# reg-board.net
KiCad netlist of a schematic drawn in EAGLE
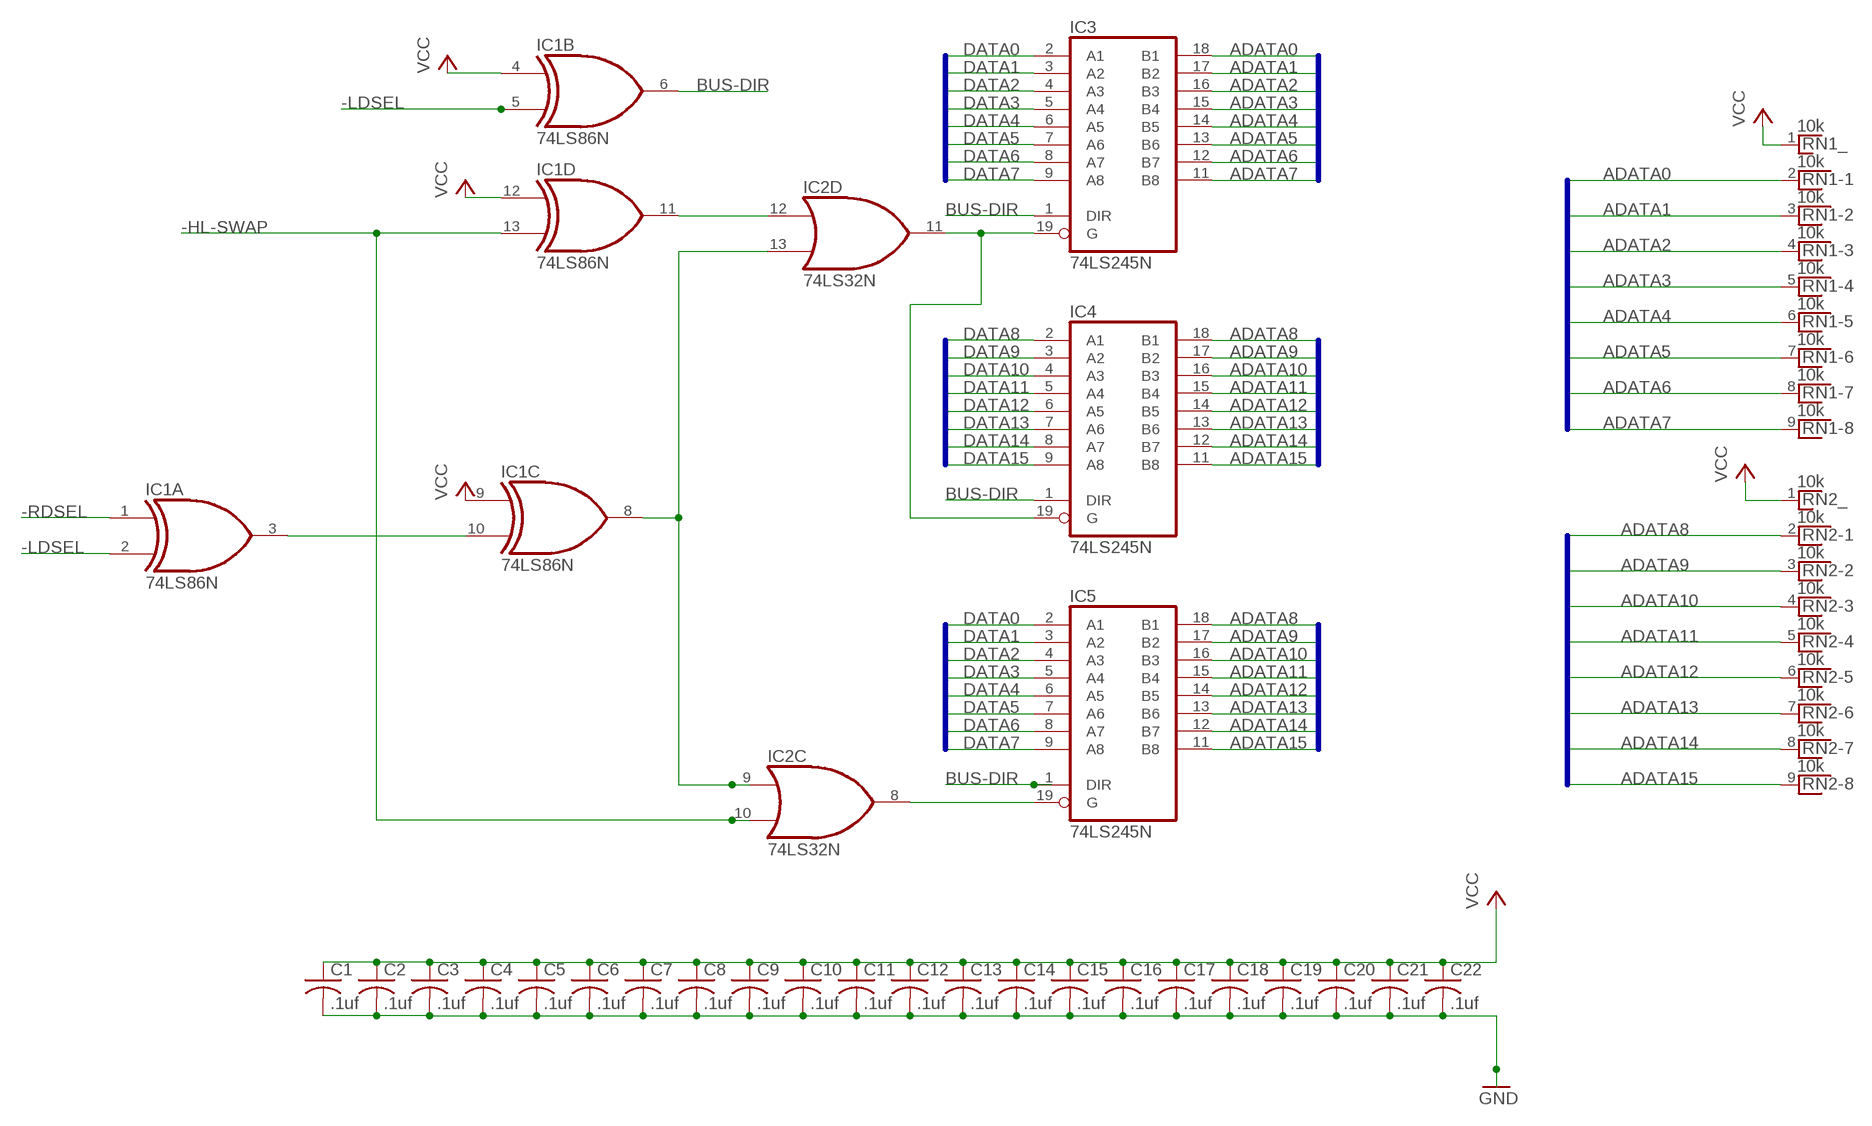
[diagram p0: schematic, sheet 1]
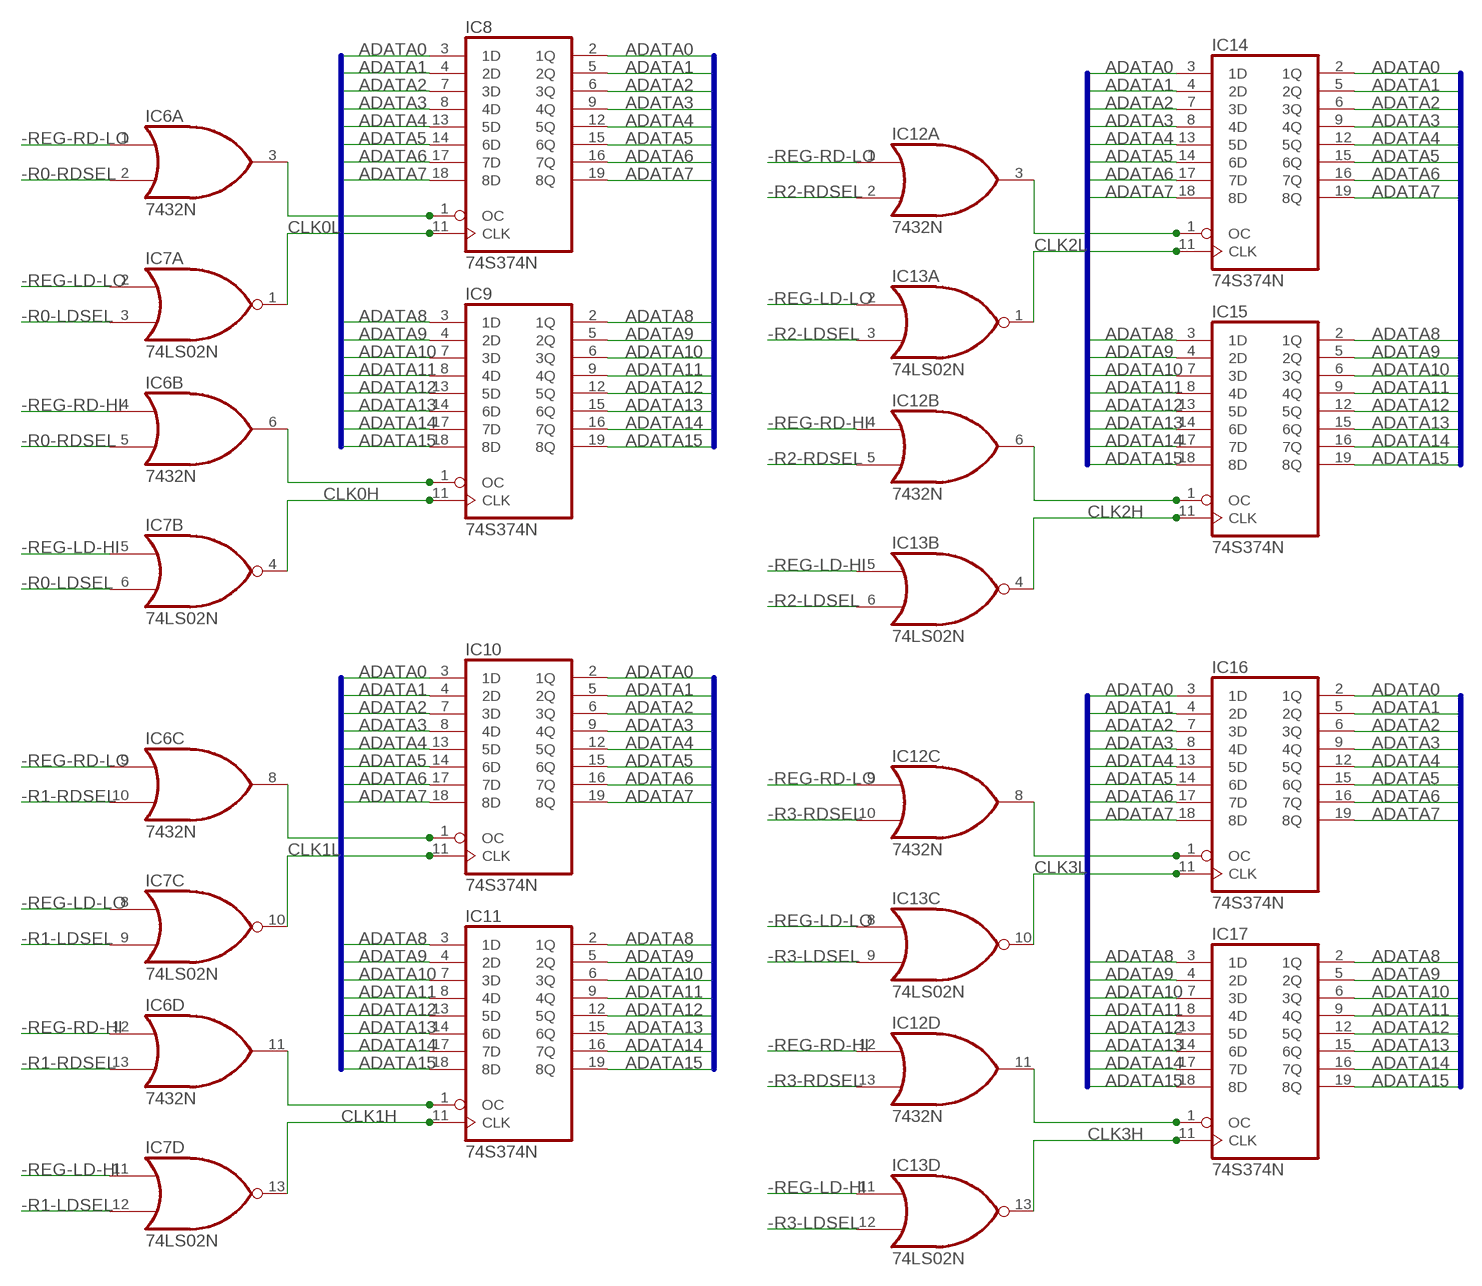
[diagram p1: schematic, sheet 2]
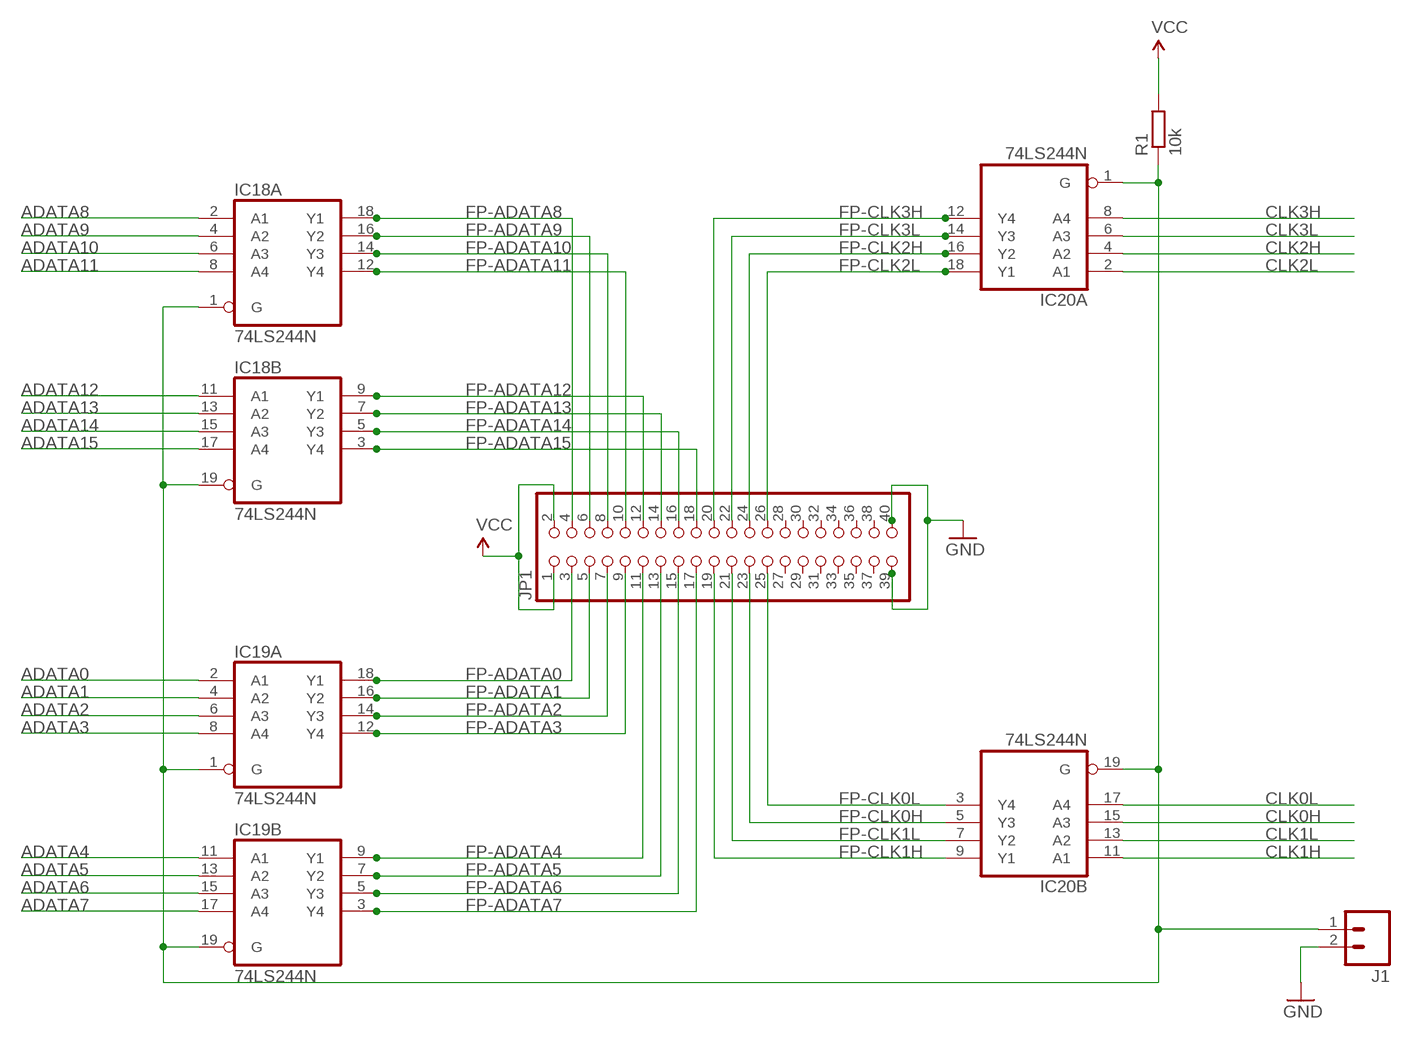
[diagram p2: schematic, sheet 3]
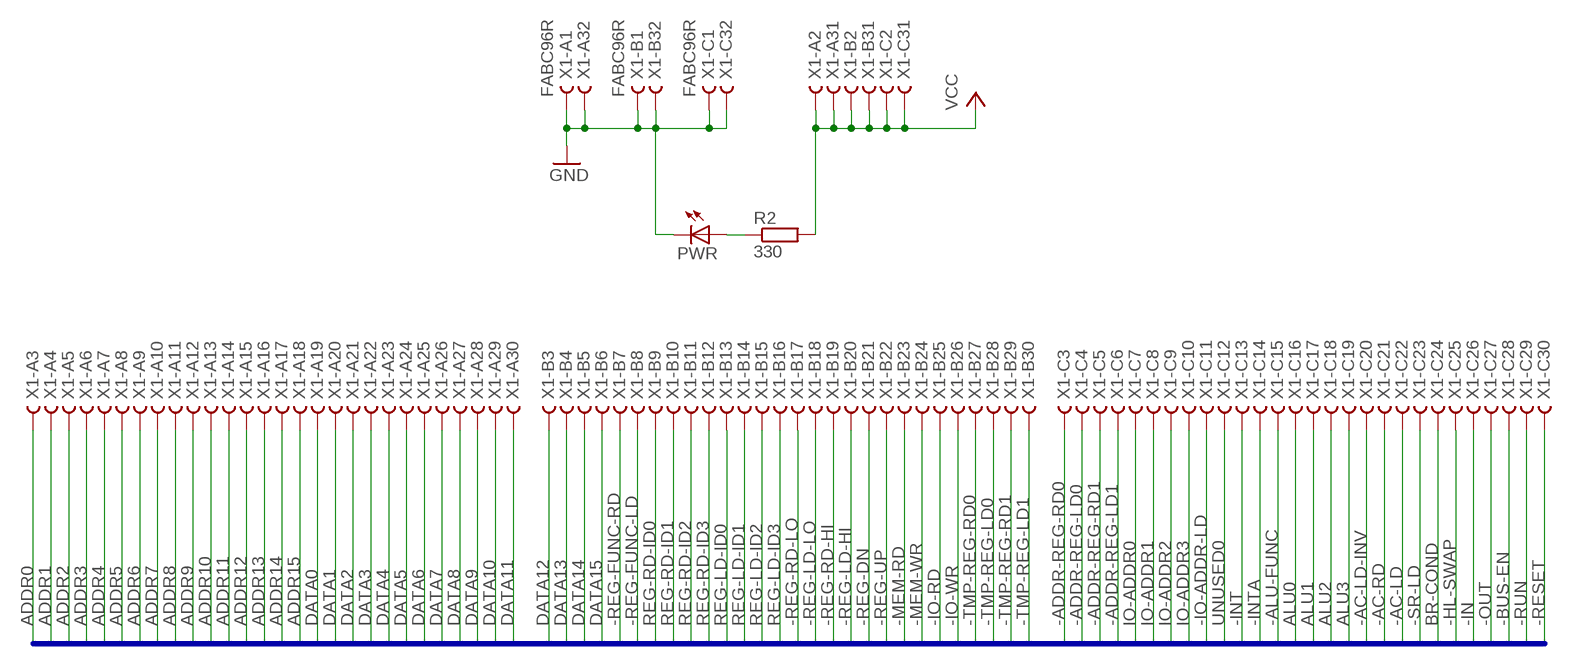
[diagram p3: schematic, sheet 4]
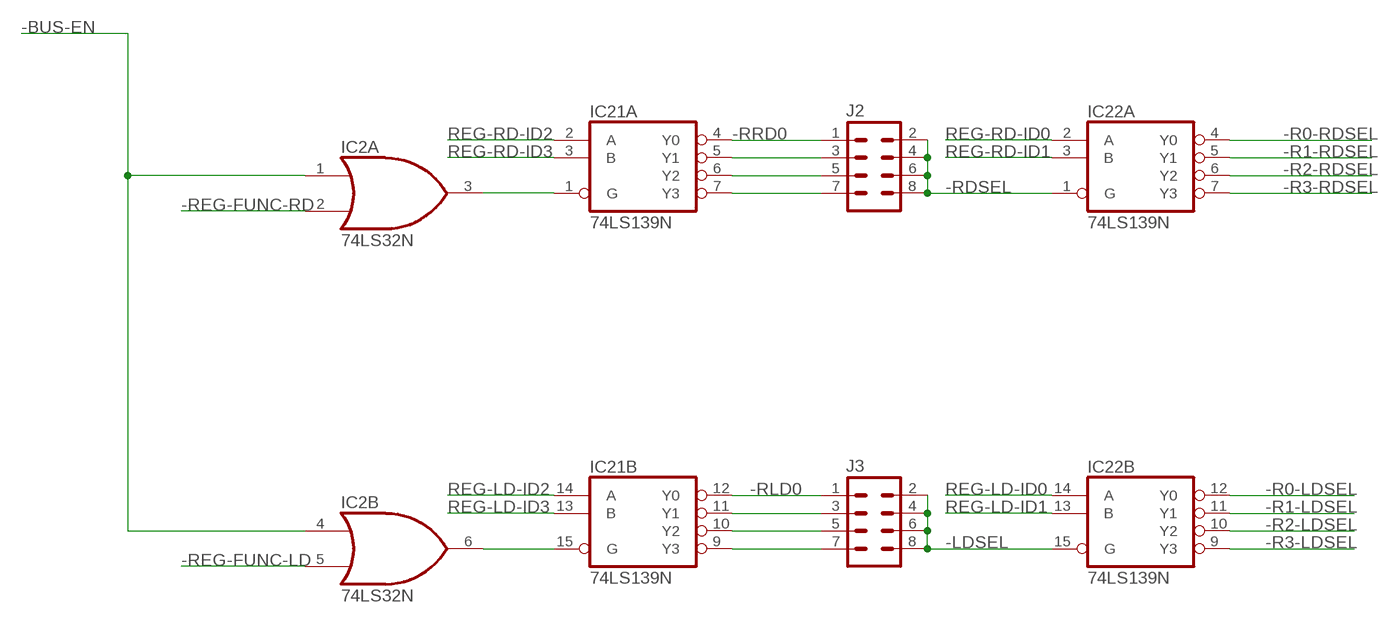
[diagram p4: schematic, sheet 5]

(export (version "E")
  (design (tool "Eeschema 10.0.6"))
  (components
    (comp (ref "PWR")
      (value "LED5MM")
      (footprint "eagle-import:LED5MM")
      (libsource (lib "eagle-import") (part "LED5MM"))
    )
    (comp (ref "R2")
      (value "330")
      (footprint "eagle-import:0207_10")
      (libsource (lib "eagle-import") (part "R0207/10"))
    )
    (comp (ref "X1")
      (value "FABC96R")
      (footprint "eagle-import:FABC96R")
      (libsource (lib "eagle-import") (part "FABC96R"))
    )
    (comp (ref "IC6")
      (value "7432N")
      (footprint "eagle-import:DIL14")
      (libsource (lib "eagle-import") (part "7432N"))
    )
    (comp (ref "IC7")
      (value "74LS02N")
      (footprint "eagle-import:DIL14")
      (libsource (lib "eagle-import") (part "7402NLS"))
    )
    (comp (ref "IC8")
      (value "74S374N")
      (footprint "eagle-import:DIL20")
      (libsource (lib "eagle-import") (part "74374NS"))
    )
    (comp (ref "IC9")
      (value "74S374N")
      (footprint "eagle-import:DIL20")
      (libsource (lib "eagle-import") (part "74374NS"))
    )
    (comp (ref "IC10")
      (value "74S374N")
      (footprint "eagle-import:DIL20")
      (libsource (lib "eagle-import") (part "74374NS"))
    )
    (comp (ref "IC11")
      (value "74S374N")
      (footprint "eagle-import:DIL20")
      (libsource (lib "eagle-import") (part "74374NS"))
    )
    (comp (ref "IC12")
      (value "7432N")
      (footprint "eagle-import:DIL14")
      (libsource (lib "eagle-import") (part "7432N"))
    )
    (comp (ref "IC13")
      (value "74LS02N")
      (footprint "eagle-import:DIL14")
      (libsource (lib "eagle-import") (part "7402NLS"))
    )
    (comp (ref "IC14")
      (value "74S374N")
      (footprint "eagle-import:DIL20")
      (libsource (lib "eagle-import") (part "74374NS"))
    )
    (comp (ref "IC15")
      (value "74S374N")
      (footprint "eagle-import:DIL20")
      (libsource (lib "eagle-import") (part "74374NS"))
    )
    (comp (ref "IC16")
      (value "74S374N")
      (footprint "eagle-import:DIL20")
      (libsource (lib "eagle-import") (part "74374NS"))
    )
    (comp (ref "IC17")
      (value "74S374N")
      (footprint "eagle-import:DIL20")
      (libsource (lib "eagle-import") (part "74374NS"))
    )
    (comp (ref "C1")
      (value ".1uf")
      (footprint "eagle-import:C025-040X050")
      (libsource (lib "eagle-import") (part "C-US025-040X050"))
    )
    (comp (ref "C2")
      (value ".1uf")
      (footprint "eagle-import:C025-040X050")
      (libsource (lib "eagle-import") (part "C-US025-040X050"))
    )
    (comp (ref "C3")
      (value ".1uf")
      (footprint "eagle-import:C025-040X050")
      (libsource (lib "eagle-import") (part "C-US025-040X050"))
    )
    (comp (ref "C4")
      (value ".1uf")
      (footprint "eagle-import:C025-040X050")
      (libsource (lib "eagle-import") (part "C-US025-040X050"))
    )
    (comp (ref "C5")
      (value ".1uf")
      (footprint "eagle-import:C025-040X050")
      (libsource (lib "eagle-import") (part "C-US025-040X050"))
    )
    (comp (ref "C6")
      (value ".1uf")
      (footprint "eagle-import:C025-040X050")
      (libsource (lib "eagle-import") (part "C-US025-040X050"))
    )
    (comp (ref "C7")
      (value ".1uf")
      (footprint "eagle-import:C025-040X050")
      (libsource (lib "eagle-import") (part "C-US025-040X050"))
    )
    (comp (ref "C8")
      (value ".1uf")
      (footprint "eagle-import:C025-040X050")
      (libsource (lib "eagle-import") (part "C-US025-040X050"))
    )
    (comp (ref "C9")
      (value ".1uf")
      (footprint "eagle-import:C025-040X050")
      (libsource (lib "eagle-import") (part "C-US025-040X050"))
    )
    (comp (ref "C10")
      (value ".1uf")
      (footprint "eagle-import:C025-040X050")
      (libsource (lib "eagle-import") (part "C-US025-040X050"))
    )
    (comp (ref "C11")
      (value ".1uf")
      (footprint "eagle-import:C025-040X050")
      (libsource (lib "eagle-import") (part "C-US025-040X050"))
    )
    (comp (ref "C12")
      (value ".1uf")
      (footprint "eagle-import:C025-040X050")
      (libsource (lib "eagle-import") (part "C-US025-040X050"))
    )
    (comp (ref "C13")
      (value ".1uf")
      (footprint "eagle-import:C025-040X050")
      (libsource (lib "eagle-import") (part "C-US025-040X050"))
    )
    (comp (ref "C14")
      (value ".1uf")
      (footprint "eagle-import:C025-040X050")
      (libsource (lib "eagle-import") (part "C-US025-040X050"))
    )
    (comp (ref "C15")
      (value ".1uf")
      (footprint "eagle-import:C025-040X050")
      (libsource (lib "eagle-import") (part "C-US025-040X050"))
    )
    (comp (ref "C16")
      (value ".1uf")
      (footprint "eagle-import:C025-040X050")
      (libsource (lib "eagle-import") (part "C-US025-040X050"))
    )
    (comp (ref "C17")
      (value ".1uf")
      (footprint "eagle-import:C025-040X050")
      (libsource (lib "eagle-import") (part "C-US025-040X050"))
    )
    (comp (ref "C18")
      (value ".1uf")
      (footprint "eagle-import:C025-040X050")
      (libsource (lib "eagle-import") (part "C-US025-040X050"))
    )
    (comp (ref "C19")
      (value ".1uf")
      (footprint "eagle-import:C025-040X050")
      (libsource (lib "eagle-import") (part "C-US025-040X050"))
    )
    (comp (ref "C20")
      (value ".1uf")
      (footprint "eagle-import:C025-040X050")
      (libsource (lib "eagle-import") (part "C-US025-040X050"))
    )
    (comp (ref "C21")
      (value ".1uf")
      (footprint "eagle-import:C025-040X050")
      (libsource (lib "eagle-import") (part "C-US025-040X050"))
    )
    (comp (ref "C22")
      (value ".1uf")
      (footprint "eagle-import:C025-040X050")
      (libsource (lib "eagle-import") (part "C-US025-040X050"))
    )
    (comp (ref "IC1")
      (value "74LS86N")
      (footprint "eagle-import:DIL14")
      (libsource (lib "eagle-import") (part "7486NLS"))
    )
    (comp (ref "IC2")
      (value "74LS32N")
      (footprint "eagle-import:DIL14")
      (libsource (lib "eagle-import") (part "74xx-us_88_7432NLS"))
    )
    (comp (ref "IC3")
      (value "74LS245N")
      (footprint "eagle-import:DIL20")
      (libsource (lib "eagle-import") (part "74245NLS"))
    )
    (comp (ref "IC4")
      (value "74LS245N")
      (footprint "eagle-import:DIL20")
      (libsource (lib "eagle-import") (part "74245NLS"))
    )
    (comp (ref "IC5")
      (value "74LS245N")
      (footprint "eagle-import:DIL20")
      (libsource (lib "eagle-import") (part "74245NLS"))
    )
    (comp (ref "RN1")
      (value "10k")
      (footprint "eagle-import:RN-9")
      (libsource (lib "eagle-import") (part "RNX8"))
    )
    (comp (ref "RN2")
      (value "10k")
      (footprint "eagle-import:RN-9")
      (libsource (lib "eagle-import") (part "RNX8"))
    )
    (comp (ref "IC18")
      (value "74LS244N")
      (footprint "eagle-import:DIL20")
      (libsource (lib "eagle-import") (part "74xx-us_74244NLS"))
    )
    (comp (ref "IC19")
      (value "74LS244N")
      (footprint "eagle-import:DIL20")
      (libsource (lib "eagle-import") (part "74xx-us_74244NLS"))
    )
    (comp (ref "IC20")
      (value "74LS244N")
      (footprint "eagle-import:DIL20")
      (libsource (lib "eagle-import") (part "74xx-us_74244NLS"))
    )
    (comp (ref "J1")
      (value "M02PTH")
      (footprint "eagle-import:1X02")
      (libsource (lib "eagle-import") (part "M02PTH"))
    )
    (comp (ref "JP1")
      (value "PINHD-2X20")
      (footprint "eagle-import:2X20")
      (libsource (lib "eagle-import") (part "PINHD-2X20"))
    )
    (comp (ref "R1")
      (value "10k")
      (footprint "eagle-import:0207_10")
      (libsource (lib "eagle-import") (part "R0207/10"))
    )
    (comp (ref "IC21")
      (value "74LS139N")
      (footprint "eagle-import:DIL16")
      (libsource (lib "eagle-import") (part "74139NLS"))
    )
    (comp (ref "IC22")
      (value "74LS139N")
      (footprint "eagle-import:DIL16")
      (libsource (lib "eagle-import") (part "74139NLS"))
    )
    (comp (ref "J2")
      (value "M04X2")
      (footprint "eagle-import:2X4")
      (libsource (lib "eagle-import") (part "M04X2"))
    )
    (comp (ref "J3")
      (value "M04X2")
      (footprint "eagle-import:2X4")
      (libsource (lib "eagle-import") (part "M04X2"))
    )
  )
  (nets
    (net (code "1") (name "-AC-LD") (class "Default")
      (node (ref "X1") (pin "C22") (pinfunction "B_C22") (pintype "passive"))
    )
    (net (code "2") (name "-AC-LD-INV") (class "Default")
      (node (ref "X1") (pin "C20") (pinfunction "B_C20") (pintype "passive"))
    )
    (net (code "3") (name "-AC-RD") (class "Default")
      (node (ref "X1") (pin "C21") (pinfunction "B_C21") (pintype "passive"))
    )
    (net (code "4") (name "-ADDR-REG-LD0") (class "Default")
      (node (ref "X1") (pin "C4") (pinfunction "B_C4") (pintype "passive"))
    )
    (net (code "5") (name "-ADDR-REG-LD1") (class "Default")
      (node (ref "X1") (pin "C6") (pinfunction "B_C6") (pintype "passive"))
    )
    (net (code "6") (name "-ADDR-REG-RD0") (class "Default")
      (node (ref "X1") (pin "C3") (pinfunction "B_C3") (pintype "passive"))
    )
    (net (code "7") (name "-ADDR-REG-RD1") (class "Default")
      (node (ref "X1") (pin "C5") (pinfunction "B_C5") (pintype "passive"))
    )
    (net (code "8") (name "-ALU-FUNC") (class "Default")
      (node (ref "X1") (pin "C15") (pinfunction "B_C15") (pintype "passive"))
    )
    (net (code "9") (name "-BUS-EN") (class "Default")
      (node (ref "IC2") (pin "1") (pinfunction "I0_1") (pintype "input"))
      (node (ref "IC2") (pin "4") (pinfunction "I0_4") (pintype "input"))
      (node (ref "X1") (pin "C28") (pinfunction "B_C28") (pintype "passive"))
    )
    (net (code "10") (name "-HL-SWAP") (class "Default")
      (node (ref "IC1") (pin "13") (pinfunction "I1_13") (pintype "input"))
      (node (ref "IC2") (pin "10") (pinfunction "I1_10") (pintype "input"))
      (node (ref "X1") (pin "C25") (pinfunction "B_C25") (pintype "passive"))
    )
    (net (code "11") (name "-IN") (class "Default")
      (node (ref "X1") (pin "C26") (pinfunction "B_C26") (pintype "passive"))
    )
    (net (code "12") (name "-INT") (class "Default")
      (node (ref "X1") (pin "C13") (pinfunction "B_C13") (pintype "passive"))
    )
    (net (code "13") (name "-INTA") (class "Default")
      (node (ref "X1") (pin "C14") (pinfunction "B_C14") (pintype "passive"))
    )
    (net (code "14") (name "-IO-ADDR-LD") (class "Default")
      (node (ref "X1") (pin "C11") (pinfunction "B_C11") (pintype "passive"))
    )
    (net (code "15") (name "-IO-RD") (class "Default")
      (node (ref "X1") (pin "B25") (pinfunction "B_B25") (pintype "passive"))
    )
    (net (code "16") (name "-IO-WR") (class "Default")
      (node (ref "X1") (pin "B26") (pinfunction "B_B26") (pintype "passive"))
    )
    (net (code "17") (name "-LDSEL") (class "Default")
      (node (ref "IC1") (pin "2") (pinfunction "I1_2") (pintype "input"))
      (node (ref "IC1") (pin "5") (pinfunction "I1_5") (pintype "input"))
      (node (ref "IC22") (pin "15") (pinfunction "G_15") (pintype "input"))
      (node (ref "J3") (pin "2") (pinfunction "2_2") (pintype "passive"))
      (node (ref "J3") (pin "4") (pinfunction "4_4") (pintype "passive"))
      (node (ref "J3") (pin "6") (pinfunction "6_6") (pintype "passive"))
      (node (ref "J3") (pin "8") (pinfunction "8_8") (pintype "passive"))
    )
    (net (code "18") (name "-MEM-RD") (class "Default")
      (node (ref "X1") (pin "B23") (pinfunction "B_B23") (pintype "passive"))
    )
    (net (code "19") (name "-MEM-WR") (class "Default")
      (node (ref "X1") (pin "B24") (pinfunction "B_B24") (pintype "passive"))
    )
    (net (code "20") (name "-OUT") (class "Default")
      (node (ref "X1") (pin "C27") (pinfunction "B_C27") (pintype "passive"))
    )
    (net (code "21") (name "-R0-LDSEL") (class "Default")
      (node (ref "IC22") (pin "12") (pinfunction "Y0_12") (pintype "output"))
      (node (ref "IC7") (pin "3") (pinfunction "I1_3") (pintype "input"))
      (node (ref "IC7") (pin "6") (pinfunction "I1_6") (pintype "input"))
    )
    (net (code "22") (name "-R0-RDSEL") (class "Default")
      (node (ref "IC22") (pin "4") (pinfunction "Y0_4") (pintype "output"))
      (node (ref "IC6") (pin "2") (pinfunction "I1_2") (pintype "input"))
      (node (ref "IC6") (pin "5") (pinfunction "I1_5") (pintype "input"))
    )
    (net (code "23") (name "-R1-LDSEL") (class "Default")
      (node (ref "IC22") (pin "11") (pinfunction "Y1_11") (pintype "output"))
      (node (ref "IC7") (pin "12") (pinfunction "I1_12") (pintype "input"))
      (node (ref "IC7") (pin "9") (pinfunction "I1_9") (pintype "input"))
    )
    (net (code "24") (name "-R1-RDSEL") (class "Default")
      (node (ref "IC22") (pin "5") (pinfunction "Y1_5") (pintype "output"))
      (node (ref "IC6") (pin "10") (pinfunction "I1_10") (pintype "input"))
      (node (ref "IC6") (pin "13") (pinfunction "I1_13") (pintype "input"))
    )
    (net (code "25") (name "-R2-LDSEL") (class "Default")
      (node (ref "IC13") (pin "3") (pinfunction "I1_3") (pintype "input"))
      (node (ref "IC13") (pin "6") (pinfunction "I1_6") (pintype "input"))
      (node (ref "IC22") (pin "10") (pinfunction "Y2_10") (pintype "output"))
    )
    (net (code "26") (name "-R2-RDSEL") (class "Default")
      (node (ref "IC12") (pin "2") (pinfunction "I1_2") (pintype "input"))
      (node (ref "IC12") (pin "5") (pinfunction "I1_5") (pintype "input"))
      (node (ref "IC22") (pin "6") (pinfunction "Y2_6") (pintype "output"))
    )
    (net (code "27") (name "-R3-LDSEL") (class "Default")
      (node (ref "IC13") (pin "12") (pinfunction "I1_12") (pintype "input"))
      (node (ref "IC13") (pin "9") (pinfunction "I1_9") (pintype "input"))
      (node (ref "IC22") (pin "9") (pinfunction "Y3_9") (pintype "output"))
    )
    (net (code "28") (name "-R3-RDSEL") (class "Default")
      (node (ref "IC12") (pin "10") (pinfunction "I1_10") (pintype "input"))
      (node (ref "IC12") (pin "13") (pinfunction "I1_13") (pintype "input"))
      (node (ref "IC22") (pin "7") (pinfunction "Y3_7") (pintype "output"))
    )
    (net (code "29") (name "-RDSEL") (class "Default")
      (node (ref "IC1") (pin "1") (pinfunction "I0_1") (pintype "input"))
      (node (ref "IC22") (pin "1") (pinfunction "G_1") (pintype "input"))
      (node (ref "J2") (pin "2") (pinfunction "2_2") (pintype "passive"))
      (node (ref "J2") (pin "4") (pinfunction "4_4") (pintype "passive"))
      (node (ref "J2") (pin "6") (pinfunction "6_6") (pintype "passive"))
      (node (ref "J2") (pin "8") (pinfunction "8_8") (pintype "passive"))
    )
    (net (code "30") (name "-REG-DN") (class "Default")
      (node (ref "X1") (pin "B21") (pinfunction "B_B21") (pintype "passive"))
    )
    (net (code "31") (name "-REG-FUNC-LD") (class "Default")
      (node (ref "IC2") (pin "5") (pinfunction "I1_5") (pintype "input"))
      (node (ref "X1") (pin "B8") (pinfunction "B_B8") (pintype "passive"))
    )
    (net (code "32") (name "-REG-FUNC-RD") (class "Default")
      (node (ref "IC2") (pin "2") (pinfunction "I1_2") (pintype "input"))
      (node (ref "X1") (pin "B7") (pinfunction "B_B7") (pintype "passive"))
    )
    (net (code "33") (name "-REG-LD-HI") (class "Default")
      (node (ref "IC13") (pin "11") (pinfunction "I0_11") (pintype "input"))
      (node (ref "IC13") (pin "5") (pinfunction "I0_5") (pintype "input"))
      (node (ref "IC7") (pin "11") (pinfunction "I0_11") (pintype "input"))
      (node (ref "IC7") (pin "5") (pinfunction "I0_5") (pintype "input"))
      (node (ref "X1") (pin "B20") (pinfunction "B_B20") (pintype "passive"))
    )
    (net (code "34") (name "-REG-LD-LO") (class "Default")
      (node (ref "IC13") (pin "2") (pinfunction "I0_2") (pintype "input"))
      (node (ref "IC13") (pin "8") (pinfunction "I0_8") (pintype "input"))
      (node (ref "IC7") (pin "2") (pinfunction "I0_2") (pintype "input"))
      (node (ref "IC7") (pin "8") (pinfunction "I0_8") (pintype "input"))
      (node (ref "X1") (pin "B18") (pinfunction "B_B18") (pintype "passive"))
    )
    (net (code "35") (name "-REG-RD-HI") (class "Default")
      (node (ref "IC12") (pin "12") (pinfunction "I0_12") (pintype "input"))
      (node (ref "IC12") (pin "4") (pinfunction "I0_4") (pintype "input"))
      (node (ref "IC6") (pin "12") (pinfunction "I0_12") (pintype "input"))
      (node (ref "IC6") (pin "4") (pinfunction "I0_4") (pintype "input"))
      (node (ref "X1") (pin "B19") (pinfunction "B_B19") (pintype "passive"))
    )
    (net (code "36") (name "-REG-RD-LO") (class "Default")
      (node (ref "IC12") (pin "1") (pinfunction "I0_1") (pintype "input"))
      (node (ref "IC12") (pin "9") (pinfunction "I0_9") (pintype "input"))
      (node (ref "IC6") (pin "1") (pinfunction "I0_1") (pintype "input"))
      (node (ref "IC6") (pin "9") (pinfunction "I0_9") (pintype "input"))
      (node (ref "X1") (pin "B17") (pinfunction "B_B17") (pintype "passive"))
    )
    (net (code "37") (name "-REG-UP") (class "Default")
      (node (ref "X1") (pin "B22") (pinfunction "B_B22") (pintype "passive"))
    )
    (net (code "38") (name "-RESET") (class "Default")
      (node (ref "X1") (pin "C30") (pinfunction "B_C30") (pintype "passive"))
    )
    (net (code "39") (name "-RLD0") (class "Default")
      (node (ref "IC21") (pin "12") (pinfunction "Y0_12") (pintype "output"))
      (node (ref "J3") (pin "1") (pinfunction "1_1") (pintype "passive"))
    )
    (net (code "40") (name "-RRD0") (class "Default")
      (node (ref "IC21") (pin "4") (pinfunction "Y0_4") (pintype "output"))
      (node (ref "J2") (pin "1") (pinfunction "1_1") (pintype "passive"))
    )
    (net (code "41") (name "-RUN") (class "Default")
      (node (ref "X1") (pin "C29") (pinfunction "B_C29") (pintype "passive"))
    )
    (net (code "42") (name "-SR-LD") (class "Default")
      (node (ref "X1") (pin "C23") (pinfunction "B_C23") (pintype "passive"))
    )
    (net (code "43") (name "-TMP-REG-LD0") (class "Default")
      (node (ref "X1") (pin "B28") (pinfunction "B_B28") (pintype "passive"))
    )
    (net (code "44") (name "-TMP-REG-LD1") (class "Default")
      (node (ref "X1") (pin "B30") (pinfunction "B_B30") (pintype "passive"))
    )
    (net (code "45") (name "-TMP-REG-RD0") (class "Default")
      (node (ref "X1") (pin "B27") (pinfunction "B_B27") (pintype "passive"))
    )
    (net (code "46") (name "-TMP-REG-RD1") (class "Default")
      (node (ref "X1") (pin "B29") (pinfunction "B_B29") (pintype "passive"))
    )
    (net (code "47") (name "ADATA0") (class "Default")
      (node (ref "IC10") (pin "2") (pinfunction "1Q_2") (pintype "tri_state"))
      (node (ref "IC10") (pin "3") (pinfunction "1D_3") (pintype "input"))
      (node (ref "IC14") (pin "2") (pinfunction "1Q_2") (pintype "tri_state"))
      (node (ref "IC14") (pin "3") (pinfunction "1D_3") (pintype "input"))
      (node (ref "IC16") (pin "2") (pinfunction "1Q_2") (pintype "tri_state"))
      (node (ref "IC16") (pin "3") (pinfunction "1D_3") (pintype "input"))
      (node (ref "IC19") (pin "2") (pinfunction "A1_2") (pintype "input"))
      (node (ref "IC3") (pin "18") (pinfunction "B1_18") (pintype "bidirectional"))
      (node (ref "IC8") (pin "2") (pinfunction "1Q_2") (pintype "tri_state"))
      (node (ref "IC8") (pin "3") (pinfunction "1D_3") (pintype "input"))
      (node (ref "RN1") (pin "2") (pinfunction "1_2") (pintype "passive"))
    )
    (net (code "48") (name "ADATA1") (class "Default")
      (node (ref "IC10") (pin "4") (pinfunction "2D_4") (pintype "input"))
      (node (ref "IC10") (pin "5") (pinfunction "2Q_5") (pintype "tri_state"))
      (node (ref "IC14") (pin "4") (pinfunction "2D_4") (pintype "input"))
      (node (ref "IC14") (pin "5") (pinfunction "2Q_5") (pintype "tri_state"))
      (node (ref "IC16") (pin "4") (pinfunction "2D_4") (pintype "input"))
      (node (ref "IC16") (pin "5") (pinfunction "2Q_5") (pintype "tri_state"))
      (node (ref "IC19") (pin "4") (pinfunction "A2_4") (pintype "input"))
      (node (ref "IC3") (pin "17") (pinfunction "B2_17") (pintype "bidirectional"))
      (node (ref "IC8") (pin "4") (pinfunction "2D_4") (pintype "input"))
      (node (ref "IC8") (pin "5") (pinfunction "2Q_5") (pintype "tri_state"))
      (node (ref "RN1") (pin "3") (pinfunction "1_3") (pintype "passive"))
    )
    (net (code "49") (name "ADATA2") (class "Default")
      (node (ref "IC10") (pin "6") (pinfunction "3Q_6") (pintype "tri_state"))
      (node (ref "IC10") (pin "7") (pinfunction "3D_7") (pintype "input"))
      (node (ref "IC14") (pin "6") (pinfunction "3Q_6") (pintype "tri_state"))
      (node (ref "IC14") (pin "7") (pinfunction "3D_7") (pintype "input"))
      (node (ref "IC16") (pin "6") (pinfunction "3Q_6") (pintype "tri_state"))
      (node (ref "IC16") (pin "7") (pinfunction "3D_7") (pintype "input"))
      (node (ref "IC19") (pin "6") (pinfunction "A3_6") (pintype "input"))
      (node (ref "IC3") (pin "16") (pinfunction "B3_16") (pintype "bidirectional"))
      (node (ref "IC8") (pin "6") (pinfunction "3Q_6") (pintype "tri_state"))
      (node (ref "IC8") (pin "7") (pinfunction "3D_7") (pintype "input"))
      (node (ref "RN1") (pin "4") (pinfunction "1_4") (pintype "passive"))
    )
    (net (code "50") (name "ADATA3") (class "Default")
      (node (ref "IC10") (pin "8") (pinfunction "4D_8") (pintype "input"))
      (node (ref "IC10") (pin "9") (pinfunction "4Q_9") (pintype "tri_state"))
      (node (ref "IC14") (pin "8") (pinfunction "4D_8") (pintype "input"))
      (node (ref "IC14") (pin "9") (pinfunction "4Q_9") (pintype "tri_state"))
      (node (ref "IC16") (pin "8") (pinfunction "4D_8") (pintype "input"))
      (node (ref "IC16") (pin "9") (pinfunction "4Q_9") (pintype "tri_state"))
      (node (ref "IC19") (pin "8") (pinfunction "A4_8") (pintype "input"))
      (node (ref "IC3") (pin "15") (pinfunction "B4_15") (pintype "bidirectional"))
      (node (ref "IC8") (pin "8") (pinfunction "4D_8") (pintype "input"))
      (node (ref "IC8") (pin "9") (pinfunction "4Q_9") (pintype "tri_state"))
      (node (ref "RN1") (pin "5") (pinfunction "1_5") (pintype "passive"))
    )
    (net (code "51") (name "ADATA4") (class "Default")
      (node (ref "IC10") (pin "12") (pinfunction "5Q_12") (pintype "tri_state"))
      (node (ref "IC10") (pin "13") (pinfunction "5D_13") (pintype "input"))
      (node (ref "IC14") (pin "12") (pinfunction "5Q_12") (pintype "tri_state"))
      (node (ref "IC14") (pin "13") (pinfunction "5D_13") (pintype "input"))
      (node (ref "IC16") (pin "12") (pinfunction "5Q_12") (pintype "tri_state"))
      (node (ref "IC16") (pin "13") (pinfunction "5D_13") (pintype "input"))
      (node (ref "IC19") (pin "11") (pinfunction "A1_11") (pintype "input"))
      (node (ref "IC3") (pin "14") (pinfunction "B5_14") (pintype "bidirectional"))
      (node (ref "IC8") (pin "12") (pinfunction "5Q_12") (pintype "tri_state"))
      (node (ref "IC8") (pin "13") (pinfunction "5D_13") (pintype "input"))
      (node (ref "RN1") (pin "6") (pinfunction "1_6") (pintype "passive"))
    )
    (net (code "52") (name "ADATA5") (class "Default")
      (node (ref "IC10") (pin "14") (pinfunction "6D_14") (pintype "input"))
      (node (ref "IC10") (pin "15") (pinfunction "6Q_15") (pintype "tri_state"))
      (node (ref "IC14") (pin "14") (pinfunction "6D_14") (pintype "input"))
      (node (ref "IC14") (pin "15") (pinfunction "6Q_15") (pintype "tri_state"))
      (node (ref "IC16") (pin "14") (pinfunction "6D_14") (pintype "input"))
      (node (ref "IC16") (pin "15") (pinfunction "6Q_15") (pintype "tri_state"))
      (node (ref "IC19") (pin "13") (pinfunction "A2_13") (pintype "input"))
      (node (ref "IC3") (pin "13") (pinfunction "B6_13") (pintype "bidirectional"))
      (node (ref "IC8") (pin "14") (pinfunction "6D_14") (pintype "input"))
      (node (ref "IC8") (pin "15") (pinfunction "6Q_15") (pintype "tri_state"))
      (node (ref "RN1") (pin "7") (pinfunction "1_7") (pintype "passive"))
    )
    (net (code "53") (name "ADATA6") (class "Default")
      (node (ref "IC10") (pin "16") (pinfunction "7Q_16") (pintype "tri_state"))
      (node (ref "IC10") (pin "17") (pinfunction "7D_17") (pintype "input"))
      (node (ref "IC14") (pin "16") (pinfunction "7Q_16") (pintype "tri_state"))
      (node (ref "IC14") (pin "17") (pinfunction "7D_17") (pintype "input"))
      (node (ref "IC16") (pin "16") (pinfunction "7Q_16") (pintype "tri_state"))
      (node (ref "IC16") (pin "17") (pinfunction "7D_17") (pintype "input"))
      (node (ref "IC19") (pin "15") (pinfunction "A3_15") (pintype "input"))
      (node (ref "IC3") (pin "12") (pinfunction "B7_12") (pintype "bidirectional"))
      (node (ref "IC8") (pin "16") (pinfunction "7Q_16") (pintype "tri_state"))
      (node (ref "IC8") (pin "17") (pinfunction "7D_17") (pintype "input"))
      (node (ref "RN1") (pin "8") (pinfunction "1_8") (pintype "passive"))
    )
    (net (code "54") (name "ADATA7") (class "Default")
      (node (ref "IC10") (pin "18") (pinfunction "8D_18") (pintype "input"))
      (node (ref "IC10") (pin "19") (pinfunction "8Q_19") (pintype "tri_state"))
      (node (ref "IC14") (pin "18") (pinfunction "8D_18") (pintype "input"))
      (node (ref "IC14") (pin "19") (pinfunction "8Q_19") (pintype "tri_state"))
      (node (ref "IC16") (pin "18") (pinfunction "8D_18") (pintype "input"))
      (node (ref "IC16") (pin "19") (pinfunction "8Q_19") (pintype "tri_state"))
      (node (ref "IC19") (pin "17") (pinfunction "A4_17") (pintype "input"))
      (node (ref "IC3") (pin "11") (pinfunction "B8_11") (pintype "bidirectional"))
      (node (ref "IC8") (pin "18") (pinfunction "8D_18") (pintype "input"))
      (node (ref "IC8") (pin "19") (pinfunction "8Q_19") (pintype "tri_state"))
      (node (ref "RN1") (pin "9") (pinfunction "1_9") (pintype "passive"))
    )
    (net (code "55") (name "ADATA8") (class "Default")
      (node (ref "IC11") (pin "2") (pinfunction "1Q_2") (pintype "tri_state"))
      (node (ref "IC11") (pin "3") (pinfunction "1D_3") (pintype "input"))
      (node (ref "IC15") (pin "2") (pinfunction "1Q_2") (pintype "tri_state"))
      (node (ref "IC15") (pin "3") (pinfunction "1D_3") (pintype "input"))
      (node (ref "IC17") (pin "2") (pinfunction "1Q_2") (pintype "tri_state"))
      (node (ref "IC17") (pin "3") (pinfunction "1D_3") (pintype "input"))
      (node (ref "IC18") (pin "2") (pinfunction "A1_2") (pintype "input"))
      (node (ref "IC4") (pin "18") (pinfunction "B1_18") (pintype "bidirectional"))
      (node (ref "IC5") (pin "18") (pinfunction "B1_18") (pintype "bidirectional"))
      (node (ref "IC9") (pin "2") (pinfunction "1Q_2") (pintype "tri_state"))
      (node (ref "IC9") (pin "3") (pinfunction "1D_3") (pintype "input"))
      (node (ref "RN2") (pin "2") (pinfunction "1_2") (pintype "passive"))
    )
    (net (code "56") (name "ADATA9") (class "Default")
      (node (ref "IC11") (pin "4") (pinfunction "2D_4") (pintype "input"))
      (node (ref "IC11") (pin "5") (pinfunction "2Q_5") (pintype "tri_state"))
      (node (ref "IC15") (pin "4") (pinfunction "2D_4") (pintype "input"))
      (node (ref "IC15") (pin "5") (pinfunction "2Q_5") (pintype "tri_state"))
      (node (ref "IC17") (pin "4") (pinfunction "2D_4") (pintype "input"))
      (node (ref "IC17") (pin "5") (pinfunction "2Q_5") (pintype "tri_state"))
      (node (ref "IC18") (pin "4") (pinfunction "A2_4") (pintype "input"))
      (node (ref "IC4") (pin "17") (pinfunction "B2_17") (pintype "bidirectional"))
      (node (ref "IC5") (pin "17") (pinfunction "B2_17") (pintype "bidirectional"))
      (node (ref "IC9") (pin "4") (pinfunction "2D_4") (pintype "input"))
      (node (ref "IC9") (pin "5") (pinfunction "2Q_5") (pintype "tri_state"))
      (node (ref "RN2") (pin "3") (pinfunction "1_3") (pintype "passive"))
    )
    (net (code "57") (name "ADATA10") (class "Default")
      (node (ref "IC11") (pin "6") (pinfunction "3Q_6") (pintype "tri_state"))
      (node (ref "IC11") (pin "7") (pinfunction "3D_7") (pintype "input"))
      (node (ref "IC15") (pin "6") (pinfunction "3Q_6") (pintype "tri_state"))
      (node (ref "IC15") (pin "7") (pinfunction "3D_7") (pintype "input"))
      (node (ref "IC17") (pin "6") (pinfunction "3Q_6") (pintype "tri_state"))
      (node (ref "IC17") (pin "7") (pinfunction "3D_7") (pintype "input"))
      (node (ref "IC18") (pin "6") (pinfunction "A3_6") (pintype "input"))
      (node (ref "IC4") (pin "16") (pinfunction "B3_16") (pintype "bidirectional"))
      (node (ref "IC5") (pin "16") (pinfunction "B3_16") (pintype "bidirectional"))
      (node (ref "IC9") (pin "6") (pinfunction "3Q_6") (pintype "tri_state"))
      (node (ref "IC9") (pin "7") (pinfunction "3D_7") (pintype "input"))
      (node (ref "RN2") (pin "4") (pinfunction "1_4") (pintype "passive"))
    )
    (net (code "58") (name "ADATA11") (class "Default")
      (node (ref "IC11") (pin "8") (pinfunction "4D_8") (pintype "input"))
      (node (ref "IC11") (pin "9") (pinfunction "4Q_9") (pintype "tri_state"))
      (node (ref "IC15") (pin "8") (pinfunction "4D_8") (pintype "input"))
      (node (ref "IC15") (pin "9") (pinfunction "4Q_9") (pintype "tri_state"))
      (node (ref "IC17") (pin "8") (pinfunction "4D_8") (pintype "input"))
      (node (ref "IC17") (pin "9") (pinfunction "4Q_9") (pintype "tri_state"))
      (node (ref "IC18") (pin "8") (pinfunction "A4_8") (pintype "input"))
      (node (ref "IC4") (pin "15") (pinfunction "B4_15") (pintype "bidirectional"))
      (node (ref "IC5") (pin "15") (pinfunction "B4_15") (pintype "bidirectional"))
      (node (ref "IC9") (pin "8") (pinfunction "4D_8") (pintype "input"))
      (node (ref "IC9") (pin "9") (pinfunction "4Q_9") (pintype "tri_state"))
      (node (ref "RN2") (pin "5") (pinfunction "1_5") (pintype "passive"))
    )
    (net (code "59") (name "ADATA12") (class "Default")
      (node (ref "IC11") (pin "12") (pinfunction "5Q_12") (pintype "tri_state"))
      (node (ref "IC11") (pin "13") (pinfunction "5D_13") (pintype "input"))
      (node (ref "IC15") (pin "12") (pinfunction "5Q_12") (pintype "tri_state"))
      (node (ref "IC15") (pin "13") (pinfunction "5D_13") (pintype "input"))
      (node (ref "IC17") (pin "12") (pinfunction "5Q_12") (pintype "tri_state"))
      (node (ref "IC17") (pin "13") (pinfunction "5D_13") (pintype "input"))
      (node (ref "IC18") (pin "11") (pinfunction "A1_11") (pintype "input"))
      (node (ref "IC4") (pin "14") (pinfunction "B5_14") (pintype "bidirectional"))
      (node (ref "IC5") (pin "14") (pinfunction "B5_14") (pintype "bidirectional"))
      (node (ref "IC9") (pin "12") (pinfunction "5Q_12") (pintype "tri_state"))
      (node (ref "IC9") (pin "13") (pinfunction "5D_13") (pintype "input"))
      (node (ref "RN2") (pin "6") (pinfunction "1_6") (pintype "passive"))
    )
    (net (code "60") (name "ADATA13") (class "Default")
      (node (ref "IC11") (pin "14") (pinfunction "6D_14") (pintype "input"))
      (node (ref "IC11") (pin "15") (pinfunction "6Q_15") (pintype "tri_state"))
      (node (ref "IC15") (pin "14") (pinfunction "6D_14") (pintype "input"))
      (node (ref "IC15") (pin "15") (pinfunction "6Q_15") (pintype "tri_state"))
      (node (ref "IC17") (pin "14") (pinfunction "6D_14") (pintype "input"))
      (node (ref "IC17") (pin "15") (pinfunction "6Q_15") (pintype "tri_state"))
      (node (ref "IC18") (pin "13") (pinfunction "A2_13") (pintype "input"))
      (node (ref "IC4") (pin "13") (pinfunction "B6_13") (pintype "bidirectional"))
      (node (ref "IC5") (pin "13") (pinfunction "B6_13") (pintype "bidirectional"))
      (node (ref "IC9") (pin "14") (pinfunction "6D_14") (pintype "input"))
      (node (ref "IC9") (pin "15") (pinfunction "6Q_15") (pintype "tri_state"))
      (node (ref "RN2") (pin "7") (pinfunction "1_7") (pintype "passive"))
    )
    (net (code "61") (name "ADATA14") (class "Default")
      (node (ref "IC11") (pin "16") (pinfunction "7Q_16") (pintype "tri_state"))
      (node (ref "IC11") (pin "17") (pinfunction "7D_17") (pintype "input"))
      (node (ref "IC15") (pin "16") (pinfunction "7Q_16") (pintype "tri_state"))
      (node (ref "IC15") (pin "17") (pinfunction "7D_17") (pintype "input"))
      (node (ref "IC17") (pin "16") (pinfunction "7Q_16") (pintype "tri_state"))
      (node (ref "IC17") (pin "17") (pinfunction "7D_17") (pintype "input"))
      (node (ref "IC18") (pin "15") (pinfunction "A3_15") (pintype "input"))
      (node (ref "IC4") (pin "12") (pinfunction "B7_12") (pintype "bidirectional"))
      (node (ref "IC5") (pin "12") (pinfunction "B7_12") (pintype "bidirectional"))
      (node (ref "IC9") (pin "16") (pinfunction "7Q_16") (pintype "tri_state"))
      (node (ref "IC9") (pin "17") (pinfunction "7D_17") (pintype "input"))
      (node (ref "RN2") (pin "8") (pinfunction "1_8") (pintype "passive"))
    )
    (net (code "62") (name "ADATA15") (class "Default")
      (node (ref "IC11") (pin "18") (pinfunction "8D_18") (pintype "input"))
      (node (ref "IC11") (pin "19") (pinfunction "8Q_19") (pintype "tri_state"))
      (node (ref "IC15") (pin "18") (pinfunction "8D_18") (pintype "input"))
      (node (ref "IC15") (pin "19") (pinfunction "8Q_19") (pintype "tri_state"))
      (node (ref "IC17") (pin "18") (pinfunction "8D_18") (pintype "input"))
      (node (ref "IC17") (pin "19") (pinfunction "8Q_19") (pintype "tri_state"))
      (node (ref "IC18") (pin "17") (pinfunction "A4_17") (pintype "input"))
      (node (ref "IC4") (pin "11") (pinfunction "B8_11") (pintype "bidirectional"))
      (node (ref "IC5") (pin "11") (pinfunction "B8_11") (pintype "bidirectional"))
      (node (ref "IC9") (pin "18") (pinfunction "8D_18") (pintype "input"))
      (node (ref "IC9") (pin "19") (pinfunction "8Q_19") (pintype "tri_state"))
      (node (ref "RN2") (pin "9") (pinfunction "1_9") (pintype "passive"))
    )
    (net (code "63") (name "ADDR0") (class "Default")
      (node (ref "X1") (pin "A3") (pinfunction "B_A3") (pintype "passive"))
    )
    (net (code "64") (name "ADDR1") (class "Default")
      (node (ref "X1") (pin "A4") (pinfunction "B_A4") (pintype "passive"))
    )
    (net (code "65") (name "ADDR2") (class "Default")
      (node (ref "X1") (pin "A5") (pinfunction "B_A5") (pintype "passive"))
    )
    (net (code "66") (name "ADDR3") (class "Default")
      (node (ref "X1") (pin "A6") (pinfunction "B_A6") (pintype "passive"))
    )
    (net (code "67") (name "ADDR4") (class "Default")
      (node (ref "X1") (pin "A7") (pinfunction "B_A7") (pintype "passive"))
    )
    (net (code "68") (name "ADDR5") (class "Default")
      (node (ref "X1") (pin "A8") (pinfunction "B_A8") (pintype "passive"))
    )
    (net (code "69") (name "ADDR6") (class "Default")
      (node (ref "X1") (pin "A9") (pinfunction "B_A9") (pintype "passive"))
    )
    (net (code "70") (name "ADDR7") (class "Default")
      (node (ref "X1") (pin "A10") (pinfunction "B_A10") (pintype "passive"))
    )
    (net (code "71") (name "ADDR8") (class "Default")
      (node (ref "X1") (pin "A11") (pinfunction "B_A11") (pintype "passive"))
    )
    (net (code "72") (name "ADDR9") (class "Default")
      (node (ref "X1") (pin "A12") (pinfunction "B_A12") (pintype "passive"))
    )
    (net (code "73") (name "ADDR10") (class "Default")
      (node (ref "X1") (pin "A13") (pinfunction "B_A13") (pintype "passive"))
    )
    (net (code "74") (name "ADDR11") (class "Default")
      (node (ref "X1") (pin "A14") (pinfunction "B_A14") (pintype "passive"))
    )
    (net (code "75") (name "ADDR12") (class "Default")
      (node (ref "X1") (pin "A15") (pinfunction "B_A15") (pintype "passive"))
    )
    (net (code "76") (name "ADDR13") (class "Default")
      (node (ref "X1") (pin "A16") (pinfunction "B_A16") (pintype "passive"))
    )
    (net (code "77") (name "ADDR14") (class "Default")
      (node (ref "X1") (pin "A17") (pinfunction "B_A17") (pintype "passive"))
    )
    (net (code "78") (name "ADDR15") (class "Default")
      (node (ref "X1") (pin "A18") (pinfunction "B_A18") (pintype "passive"))
    )
    (net (code "79") (name "ALU0") (class "Default")
      (node (ref "X1") (pin "C16") (pinfunction "B_C16") (pintype "passive"))
    )
    (net (code "80") (name "ALU1") (class "Default")
      (node (ref "X1") (pin "C17") (pinfunction "B_C17") (pintype "passive"))
    )
    (net (code "81") (name "ALU2") (class "Default")
      (node (ref "X1") (pin "C18") (pinfunction "B_C18") (pintype "passive"))
    )
    (net (code "82") (name "ALU3") (class "Default")
      (node (ref "X1") (pin "C19") (pinfunction "B_C19") (pintype "passive"))
    )
    (net (code "83") (name "BR-COND") (class "Default")
      (node (ref "X1") (pin "C24") (pinfunction "B_C24") (pintype "passive"))
    )
    (net (code "84") (name "BUS-DIR") (class "Default")
      (node (ref "IC1") (pin "6") (pinfunction "O_6") (pintype "output"))
      (node (ref "IC3") (pin "1") (pinfunction "DIR_1") (pintype "input"))
      (node (ref "IC4") (pin "1") (pinfunction "DIR_1") (pintype "input"))
      (node (ref "IC5") (pin "1") (pinfunction "DIR_1") (pintype "input"))
    )
    (net (code "85") (name "CLK0H") (class "Default")
      (node (ref "IC20") (pin "15") (pinfunction "A3_15") (pintype "input"))
      (node (ref "IC7") (pin "4") (pinfunction "O_4") (pintype "output"))
      (node (ref "IC9") (pin "11") (pinfunction "CLK_11") (pintype "input"))
    )
    (net (code "86") (name "CLK0L") (class "Default")
      (node (ref "IC20") (pin "17") (pinfunction "A4_17") (pintype "input"))
      (node (ref "IC7") (pin "1") (pinfunction "O_1") (pintype "output"))
      (node (ref "IC8") (pin "11") (pinfunction "CLK_11") (pintype "input"))
    )
    (net (code "87") (name "CLK1H") (class "Default")
      (node (ref "IC11") (pin "11") (pinfunction "CLK_11") (pintype "input"))
      (node (ref "IC20") (pin "11") (pinfunction "A1_11") (pintype "input"))
      (node (ref "IC7") (pin "13") (pinfunction "O_13") (pintype "output"))
    )
    (net (code "88") (name "CLK1L") (class "Default")
      (node (ref "IC10") (pin "11") (pinfunction "CLK_11") (pintype "input"))
      (node (ref "IC20") (pin "13") (pinfunction "A2_13") (pintype "input"))
      (node (ref "IC7") (pin "10") (pinfunction "O_10") (pintype "output"))
    )
    (net (code "89") (name "CLK2H") (class "Default")
      (node (ref "IC13") (pin "4") (pinfunction "O_4") (pintype "output"))
      (node (ref "IC15") (pin "11") (pinfunction "CLK_11") (pintype "input"))
      (node (ref "IC20") (pin "4") (pinfunction "A2_4") (pintype "input"))
    )
    (net (code "90") (name "CLK2L") (class "Default")
      (node (ref "IC13") (pin "1") (pinfunction "O_1") (pintype "output"))
      (node (ref "IC14") (pin "11") (pinfunction "CLK_11") (pintype "input"))
      (node (ref "IC20") (pin "2") (pinfunction "A1_2") (pintype "input"))
    )
    (net (code "91") (name "CLK3H") (class "Default")
      (node (ref "IC13") (pin "13") (pinfunction "O_13") (pintype "output"))
      (node (ref "IC17") (pin "11") (pinfunction "CLK_11") (pintype "input"))
      (node (ref "IC20") (pin "8") (pinfunction "A4_8") (pintype "input"))
    )
    (net (code "92") (name "CLK3L") (class "Default")
      (node (ref "IC13") (pin "10") (pinfunction "O_10") (pintype "output"))
      (node (ref "IC16") (pin "11") (pinfunction "CLK_11") (pintype "input"))
      (node (ref "IC20") (pin "6") (pinfunction "A3_6") (pintype "input"))
    )
    (net (code "93") (name "DATA0") (class "Default")
      (node (ref "IC3") (pin "2") (pinfunction "A1_2") (pintype "bidirectional"))
      (node (ref "IC5") (pin "2") (pinfunction "A1_2") (pintype "bidirectional"))
      (node (ref "X1") (pin "A19") (pinfunction "B_A19") (pintype "passive"))
    )
    (net (code "94") (name "DATA1") (class "Default")
      (node (ref "IC3") (pin "3") (pinfunction "A2_3") (pintype "bidirectional"))
      (node (ref "IC5") (pin "3") (pinfunction "A2_3") (pintype "bidirectional"))
      (node (ref "X1") (pin "A20") (pinfunction "B_A20") (pintype "passive"))
    )
    (net (code "95") (name "DATA2") (class "Default")
      (node (ref "IC3") (pin "4") (pinfunction "A3_4") (pintype "bidirectional"))
      (node (ref "IC5") (pin "4") (pinfunction "A3_4") (pintype "bidirectional"))
      (node (ref "X1") (pin "A21") (pinfunction "B_A21") (pintype "passive"))
    )
    (net (code "96") (name "DATA3") (class "Default")
      (node (ref "IC3") (pin "5") (pinfunction "A4_5") (pintype "bidirectional"))
      (node (ref "IC5") (pin "5") (pinfunction "A4_5") (pintype "bidirectional"))
      (node (ref "X1") (pin "A22") (pinfunction "B_A22") (pintype "passive"))
    )
    (net (code "97") (name "DATA4") (class "Default")
      (node (ref "IC3") (pin "6") (pinfunction "A5_6") (pintype "bidirectional"))
      (node (ref "IC5") (pin "6") (pinfunction "A5_6") (pintype "bidirectional"))
      (node (ref "X1") (pin "A23") (pinfunction "B_A23") (pintype "passive"))
    )
    (net (code "98") (name "DATA5") (class "Default")
      (node (ref "IC3") (pin "7") (pinfunction "A6_7") (pintype "bidirectional"))
      (node (ref "IC5") (pin "7") (pinfunction "A6_7") (pintype "bidirectional"))
      (node (ref "X1") (pin "A24") (pinfunction "B_A24") (pintype "passive"))
    )
    (net (code "99") (name "DATA6") (class "Default")
      (node (ref "IC3") (pin "8") (pinfunction "A7_8") (pintype "bidirectional"))
      (node (ref "IC5") (pin "8") (pinfunction "A7_8") (pintype "bidirectional"))
      (node (ref "X1") (pin "A25") (pinfunction "B_A25") (pintype "passive"))
    )
    (net (code "100") (name "DATA7") (class "Default")
      (node (ref "IC3") (pin "9") (pinfunction "A8_9") (pintype "bidirectional"))
      (node (ref "IC5") (pin "9") (pinfunction "A8_9") (pintype "bidirectional"))
      (node (ref "X1") (pin "A26") (pinfunction "B_A26") (pintype "passive"))
    )
    (net (code "101") (name "DATA8") (class "Default")
      (node (ref "IC4") (pin "2") (pinfunction "A1_2") (pintype "bidirectional"))
      (node (ref "X1") (pin "A27") (pinfunction "B_A27") (pintype "passive"))
    )
    (net (code "102") (name "DATA9") (class "Default")
      (node (ref "IC4") (pin "3") (pinfunction "A2_3") (pintype "bidirectional"))
      (node (ref "X1") (pin "A28") (pinfunction "B_A28") (pintype "passive"))
    )
    (net (code "103") (name "DATA10") (class "Default")
      (node (ref "IC4") (pin "4") (pinfunction "A3_4") (pintype "bidirectional"))
      (node (ref "X1") (pin "A29") (pinfunction "B_A29") (pintype "passive"))
    )
    (net (code "104") (name "DATA11") (class "Default")
      (node (ref "IC4") (pin "5") (pinfunction "A4_5") (pintype "bidirectional"))
      (node (ref "X1") (pin "A30") (pinfunction "B_A30") (pintype "passive"))
    )
    (net (code "105") (name "DATA12") (class "Default")
      (node (ref "IC4") (pin "6") (pinfunction "A5_6") (pintype "bidirectional"))
      (node (ref "X1") (pin "B3") (pinfunction "B_B3") (pintype "passive"))
    )
    (net (code "106") (name "DATA13") (class "Default")
      (node (ref "IC4") (pin "7") (pinfunction "A6_7") (pintype "bidirectional"))
      (node (ref "X1") (pin "B4") (pinfunction "B_B4") (pintype "passive"))
    )
    (net (code "107") (name "DATA14") (class "Default")
      (node (ref "IC4") (pin "8") (pinfunction "A7_8") (pintype "bidirectional"))
      (node (ref "X1") (pin "B5") (pinfunction "B_B5") (pintype "passive"))
    )
    (net (code "108") (name "DATA15") (class "Default")
      (node (ref "IC4") (pin "9") (pinfunction "A8_9") (pintype "bidirectional"))
      (node (ref "X1") (pin "B6") (pinfunction "B_B6") (pintype "passive"))
    )
    (net (code "109") (name "FP-ADATA0") (class "Default")
      (node (ref "IC19") (pin "18") (pinfunction "Y1_18") (pintype "tri_state"))
      (node (ref "JP1") (pin "3") (pinfunction "3_3") (pintype "passive"))
    )
    (net (code "110") (name "FP-ADATA1") (class "Default")
      (node (ref "IC19") (pin "16") (pinfunction "Y2_16") (pintype "tri_state"))
      (node (ref "JP1") (pin "5") (pinfunction "5_5") (pintype "passive"))
    )
    (net (code "111") (name "FP-ADATA2") (class "Default")
      (node (ref "IC19") (pin "14") (pinfunction "Y3_14") (pintype "tri_state"))
      (node (ref "JP1") (pin "7") (pinfunction "7_7") (pintype "passive"))
    )
    (net (code "112") (name "FP-ADATA3") (class "Default")
      (node (ref "IC19") (pin "12") (pinfunction "Y4_12") (pintype "tri_state"))
      (node (ref "JP1") (pin "9") (pinfunction "9_9") (pintype "passive"))
    )
    (net (code "113") (name "FP-ADATA4") (class "Default")
      (node (ref "IC19") (pin "9") (pinfunction "Y1_9") (pintype "tri_state"))
      (node (ref "JP1") (pin "11") (pinfunction "11_11") (pintype "passive"))
    )
    (net (code "114") (name "FP-ADATA5") (class "Default")
      (node (ref "IC19") (pin "7") (pinfunction "Y2_7") (pintype "tri_state"))
      (node (ref "JP1") (pin "13") (pinfunction "13_13") (pintype "passive"))
    )
    (net (code "115") (name "FP-ADATA6") (class "Default")
      (node (ref "IC19") (pin "5") (pinfunction "Y3_5") (pintype "tri_state"))
      (node (ref "JP1") (pin "15") (pinfunction "15_15") (pintype "passive"))
    )
    (net (code "116") (name "FP-ADATA7") (class "Default")
      (node (ref "IC19") (pin "3") (pinfunction "Y4_3") (pintype "tri_state"))
      (node (ref "JP1") (pin "17") (pinfunction "17_17") (pintype "passive"))
    )
    (net (code "117") (name "FP-ADATA8") (class "Default")
      (node (ref "IC18") (pin "18") (pinfunction "Y1_18") (pintype "tri_state"))
      (node (ref "JP1") (pin "4") (pinfunction "4_4") (pintype "passive"))
    )
    (net (code "118") (name "FP-ADATA9") (class "Default")
      (node (ref "IC18") (pin "16") (pinfunction "Y2_16") (pintype "tri_state"))
      (node (ref "JP1") (pin "6") (pinfunction "6_6") (pintype "passive"))
    )
    (net (code "119") (name "FP-ADATA10") (class "Default")
      (node (ref "IC18") (pin "14") (pinfunction "Y3_14") (pintype "tri_state"))
      (node (ref "JP1") (pin "8") (pinfunction "8_8") (pintype "passive"))
    )
    (net (code "120") (name "FP-ADATA11") (class "Default")
      (node (ref "IC18") (pin "12") (pinfunction "Y4_12") (pintype "tri_state"))
      (node (ref "JP1") (pin "10") (pinfunction "10_10") (pintype "passive"))
    )
    (net (code "121") (name "FP-ADATA12") (class "Default")
      (node (ref "IC18") (pin "9") (pinfunction "Y1_9") (pintype "tri_state"))
      (node (ref "JP1") (pin "12") (pinfunction "12_12") (pintype "passive"))
    )
    (net (code "122") (name "FP-ADATA13") (class "Default")
      (node (ref "IC18") (pin "7") (pinfunction "Y2_7") (pintype "tri_state"))
      (node (ref "JP1") (pin "14") (pinfunction "14_14") (pintype "passive"))
    )
    (net (code "123") (name "FP-ADATA14") (class "Default")
      (node (ref "IC18") (pin "5") (pinfunction "Y3_5") (pintype "tri_state"))
      (node (ref "JP1") (pin "16") (pinfunction "16_16") (pintype "passive"))
    )
    (net (code "124") (name "FP-ADATA15") (class "Default")
      (node (ref "IC18") (pin "3") (pinfunction "Y4_3") (pintype "tri_state"))
      (node (ref "JP1") (pin "18") (pinfunction "18_18") (pintype "passive"))
    )
    (net (code "125") (name "FP-CLK0H") (class "Default")
      (node (ref "IC20") (pin "5") (pinfunction "Y3_5") (pintype "tri_state"))
      (node (ref "JP1") (pin "23") (pinfunction "23_23") (pintype "passive"))
    )
    (net (code "126") (name "FP-CLK0L") (class "Default")
      (node (ref "IC20") (pin "3") (pinfunction "Y4_3") (pintype "tri_state"))
      (node (ref "JP1") (pin "25") (pinfunction "25_25") (pintype "passive"))
    )
    (net (code "127") (name "FP-CLK1H") (class "Default")
      (node (ref "IC20") (pin "9") (pinfunction "Y1_9") (pintype "tri_state"))
      (node (ref "JP1") (pin "19") (pinfunction "19_19") (pintype "passive"))
    )
    (net (code "128") (name "FP-CLK1L") (class "Default")
      (node (ref "IC20") (pin "7") (pinfunction "Y2_7") (pintype "tri_state"))
      (node (ref "JP1") (pin "21") (pinfunction "21_21") (pintype "passive"))
    )
    (net (code "129") (name "FP-CLK2H") (class "Default")
      (node (ref "IC20") (pin "16") (pinfunction "Y2_16") (pintype "tri_state"))
      (node (ref "JP1") (pin "24") (pinfunction "24_24") (pintype "passive"))
    )
    (net (code "130") (name "FP-CLK2L") (class "Default")
      (node (ref "IC20") (pin "18") (pinfunction "Y1_18") (pintype "tri_state"))
      (node (ref "JP1") (pin "26") (pinfunction "26_26") (pintype "passive"))
    )
    (net (code "131") (name "FP-CLK3H") (class "Default")
      (node (ref "IC20") (pin "12") (pinfunction "Y4_12") (pintype "tri_state"))
      (node (ref "JP1") (pin "20") (pinfunction "20_20") (pintype "passive"))
    )
    (net (code "132") (name "FP-CLK3L") (class "Default")
      (node (ref "IC20") (pin "14") (pinfunction "Y3_14") (pintype "tri_state"))
      (node (ref "JP1") (pin "22") (pinfunction "22_22") (pintype "passive"))
    )
    (net (code "133") (name "GND") (class "Default")
      (node (ref "C1") (pin "2") (pinfunction "2_2") (pintype "passive"))
      (node (ref "C10") (pin "2") (pinfunction "2_2") (pintype "passive"))
      (node (ref "C11") (pin "2") (pinfunction "2_2") (pintype "passive"))
      (node (ref "C12") (pin "2") (pinfunction "2_2") (pintype "passive"))
      (node (ref "C13") (pin "2") (pinfunction "2_2") (pintype "passive"))
      (node (ref "C14") (pin "2") (pinfunction "2_2") (pintype "passive"))
      (node (ref "C15") (pin "2") (pinfunction "2_2") (pintype "passive"))
      (node (ref "C16") (pin "2") (pinfunction "2_2") (pintype "passive"))
      (node (ref "C17") (pin "2") (pinfunction "2_2") (pintype "passive"))
      (node (ref "C18") (pin "2") (pinfunction "2_2") (pintype "passive"))
      (node (ref "C19") (pin "2") (pinfunction "2_2") (pintype "passive"))
      (node (ref "C2") (pin "2") (pinfunction "2_2") (pintype "passive"))
      (node (ref "C20") (pin "2") (pinfunction "2_2") (pintype "passive"))
      (node (ref "C21") (pin "2") (pinfunction "2_2") (pintype "passive"))
      (node (ref "C22") (pin "2") (pinfunction "2_2") (pintype "passive"))
      (node (ref "C3") (pin "2") (pinfunction "2_2") (pintype "passive"))
      (node (ref "C4") (pin "2") (pinfunction "2_2") (pintype "passive"))
      (node (ref "C5") (pin "2") (pinfunction "2_2") (pintype "passive"))
      (node (ref "C6") (pin "2") (pinfunction "2_2") (pintype "passive"))
      (node (ref "C7") (pin "2") (pinfunction "2_2") (pintype "passive"))
      (node (ref "C8") (pin "2") (pinfunction "2_2") (pintype "passive"))
      (node (ref "C9") (pin "2") (pinfunction "2_2") (pintype "passive"))
      (node (ref "J1") (pin "2") (pinfunction "2_2") (pintype "passive"))
      (node (ref "JP1") (pin "39") (pinfunction "39_39") (pintype "passive"))
      (node (ref "JP1") (pin "40") (pinfunction "40_40") (pintype "passive"))
      (node (ref "PWR") (pin "K") (pinfunction "C_K") (pintype "passive"))
      (node (ref "X1") (pin "A1") (pinfunction "B_A1") (pintype "passive"))
      (node (ref "X1") (pin "A32") (pinfunction "B_A32") (pintype "passive"))
      (node (ref "X1") (pin "B1") (pinfunction "B_B1") (pintype "passive"))
      (node (ref "X1") (pin "B32") (pinfunction "B_B32") (pintype "passive"))
      (node (ref "X1") (pin "C1") (pinfunction "B_C1") (pintype "passive"))
      (node (ref "X1") (pin "C32") (pinfunction "B_C32") (pintype "passive"))
    )
    (net (code "134") (name "IO-ADDR0") (class "Default")
      (node (ref "X1") (pin "C7") (pinfunction "B_C7") (pintype "passive"))
    )
    (net (code "135") (name "IO-ADDR1") (class "Default")
      (node (ref "X1") (pin "C8") (pinfunction "B_C8") (pintype "passive"))
    )
    (net (code "136") (name "IO-ADDR2") (class "Default")
      (node (ref "X1") (pin "C9") (pinfunction "B_C9") (pintype "passive"))
    )
    (net (code "137") (name "IO-ADDR3") (class "Default")
      (node (ref "X1") (pin "C10") (pinfunction "B_C10") (pintype "passive"))
    )
    (net (code "138") (name "Net-(IC1A-O)") (class "Default")
      (node (ref "IC1") (pin "10") (pinfunction "I1_10") (pintype "input"))
      (node (ref "IC1") (pin "3") (pinfunction "O_3") (pintype "output"))
    )
    (net (code "139") (name "Net-(IC1C-O)") (class "Default")
      (node (ref "IC1") (pin "8") (pinfunction "O_8") (pintype "output"))
      (node (ref "IC2") (pin "13") (pinfunction "I1_13") (pintype "input"))
      (node (ref "IC2") (pin "9") (pinfunction "I0_9") (pintype "input"))
    )
    (net (code "140") (name "Net-(IC1D-O)") (class "Default")
      (node (ref "IC1") (pin "11") (pinfunction "O_11") (pintype "output"))
      (node (ref "IC2") (pin "12") (pinfunction "I0_12") (pintype "input"))
    )
    (net (code "141") (name "Net-(IC2C-O)") (class "Default")
      (node (ref "IC2") (pin "8") (pinfunction "O_8") (pintype "output"))
      (node (ref "IC5") (pin "19") (pinfunction "G_19") (pintype "input"))
    )
    (net (code "142") (name "Net-(IC2D-O)") (class "Default")
      (node (ref "IC2") (pin "11") (pinfunction "O_11") (pintype "output"))
      (node (ref "IC3") (pin "19") (pinfunction "G_19") (pintype "input"))
      (node (ref "IC4") (pin "19") (pinfunction "G_19") (pintype "input"))
    )
    (net (code "143") (name "Net-(IC6A-O)") (class "Default")
      (node (ref "IC6") (pin "3") (pinfunction "O_3") (pintype "output"))
      (node (ref "IC8") (pin "1") (pinfunction "OC_1") (pintype "input"))
    )
    (net (code "144") (name "Net-(IC6B-O)") (class "Default")
      (node (ref "IC6") (pin "6") (pinfunction "O_6") (pintype "output"))
      (node (ref "IC9") (pin "1") (pinfunction "OC_1") (pintype "input"))
    )
    (net (code "145") (name "Net-(IC10A-OC)") (class "Default")
      (node (ref "IC10") (pin "1") (pinfunction "OC_1") (pintype "input"))
      (node (ref "IC6") (pin "8") (pinfunction "O_8") (pintype "output"))
    )
    (net (code "146") (name "Net-(IC11A-OC)") (class "Default")
      (node (ref "IC11") (pin "1") (pinfunction "OC_1") (pintype "input"))
      (node (ref "IC6") (pin "11") (pinfunction "O_11") (pintype "output"))
    )
    (net (code "147") (name "Net-(IC12A-O)") (class "Default")
      (node (ref "IC12") (pin "3") (pinfunction "O_3") (pintype "output"))
      (node (ref "IC14") (pin "1") (pinfunction "OC_1") (pintype "input"))
    )
    (net (code "148") (name "Net-(IC12B-O)") (class "Default")
      (node (ref "IC12") (pin "6") (pinfunction "O_6") (pintype "output"))
      (node (ref "IC15") (pin "1") (pinfunction "OC_1") (pintype "input"))
    )
    (net (code "149") (name "Net-(IC12C-O)") (class "Default")
      (node (ref "IC12") (pin "8") (pinfunction "O_8") (pintype "output"))
      (node (ref "IC16") (pin "1") (pinfunction "OC_1") (pintype "input"))
    )
    (net (code "150") (name "Net-(IC12D-O)") (class "Default")
      (node (ref "IC12") (pin "11") (pinfunction "O_11") (pintype "output"))
      (node (ref "IC17") (pin "1") (pinfunction "OC_1") (pintype "input"))
    )
    (net (code "151") (name "Net-(IC18A-G)") (class "Default")
      (node (ref "IC18") (pin "1") (pinfunction "G_1") (pintype "input"))
      (node (ref "IC18") (pin "19") (pinfunction "G_19") (pintype "input"))
      (node (ref "IC19") (pin "1") (pinfunction "G_1") (pintype "input"))
      (node (ref "IC19") (pin "19") (pinfunction "G_19") (pintype "input"))
      (node (ref "IC20") (pin "1") (pinfunction "G_1") (pintype "input"))
      (node (ref "IC20") (pin "19") (pinfunction "G_19") (pintype "input"))
      (node (ref "J1") (pin "1") (pinfunction "1_1") (pintype "passive"))
      (node (ref "R1") (pin "1") (pinfunction "1_1") (pintype "passive"))
    )
    (net (code "152") (name "Net-(IC21A-G)") (class "Default")
      (node (ref "IC2") (pin "3") (pinfunction "O_3") (pintype "output"))
      (node (ref "IC21") (pin "1") (pinfunction "G_1") (pintype "input"))
    )
    (net (code "153") (name "Net-(IC21A-Y1)") (class "Default")
      (node (ref "IC21") (pin "5") (pinfunction "Y1_5") (pintype "output"))
      (node (ref "J2") (pin "3") (pinfunction "3_3") (pintype "passive"))
    )
    (net (code "154") (name "Net-(IC21A-Y2)") (class "Default")
      (node (ref "IC21") (pin "6") (pinfunction "Y2_6") (pintype "output"))
      (node (ref "J2") (pin "5") (pinfunction "5_5") (pintype "passive"))
    )
    (net (code "155") (name "Net-(IC21A-Y3)") (class "Default")
      (node (ref "IC21") (pin "7") (pinfunction "Y3_7") (pintype "output"))
      (node (ref "J2") (pin "7") (pinfunction "7_7") (pintype "passive"))
    )
    (net (code "156") (name "Net-(IC21B-G)") (class "Default")
      (node (ref "IC2") (pin "6") (pinfunction "O_6") (pintype "output"))
      (node (ref "IC21") (pin "15") (pinfunction "G_15") (pintype "input"))
    )
    (net (code "157") (name "Net-(IC21B-Y1)") (class "Default")
      (node (ref "IC21") (pin "11") (pinfunction "Y1_11") (pintype "output"))
      (node (ref "J3") (pin "3") (pinfunction "3_3") (pintype "passive"))
    )
    (net (code "158") (name "Net-(IC21B-Y2)") (class "Default")
      (node (ref "IC21") (pin "10") (pinfunction "Y2_10") (pintype "output"))
      (node (ref "J3") (pin "5") (pinfunction "5_5") (pintype "passive"))
    )
    (net (code "159") (name "Net-(IC21B-Y3)") (class "Default")
      (node (ref "IC21") (pin "9") (pinfunction "Y3_9") (pintype "output"))
      (node (ref "J3") (pin "7") (pinfunction "7_7") (pintype "passive"))
    )
    (net (code "160") (name "Net-(PWR-PadA)") (class "Default")
      (node (ref "PWR") (pin "A") (pinfunction "A_A") (pintype "passive"))
      (node (ref "R2") (pin "1") (pinfunction "1_1") (pintype "passive"))
    )
    (net (code "161") (name "REG-LD-ID0") (class "Default")
      (node (ref "IC22") (pin "14") (pinfunction "A_14") (pintype "input"))
      (node (ref "X1") (pin "B13") (pinfunction "B_B13") (pintype "passive"))
    )
    (net (code "162") (name "REG-LD-ID1") (class "Default")
      (node (ref "IC22") (pin "13") (pinfunction "B_13") (pintype "input"))
      (node (ref "X1") (pin "B14") (pinfunction "B_B14") (pintype "passive"))
    )
    (net (code "163") (name "REG-LD-ID2") (class "Default")
      (node (ref "IC21") (pin "14") (pinfunction "A_14") (pintype "input"))
      (node (ref "X1") (pin "B15") (pinfunction "B_B15") (pintype "passive"))
    )
    (net (code "164") (name "REG-LD-ID3") (class "Default")
      (node (ref "IC21") (pin "13") (pinfunction "B_13") (pintype "input"))
      (node (ref "X1") (pin "B16") (pinfunction "B_B16") (pintype "passive"))
    )
    (net (code "165") (name "REG-RD-ID0") (class "Default")
      (node (ref "IC22") (pin "2") (pinfunction "A_2") (pintype "input"))
      (node (ref "X1") (pin "B9") (pinfunction "B_B9") (pintype "passive"))
    )
    (net (code "166") (name "REG-RD-ID1") (class "Default")
      (node (ref "IC22") (pin "3") (pinfunction "B_3") (pintype "input"))
      (node (ref "X1") (pin "B10") (pinfunction "B_B10") (pintype "passive"))
    )
    (net (code "167") (name "REG-RD-ID2") (class "Default")
      (node (ref "IC21") (pin "2") (pinfunction "A_2") (pintype "input"))
      (node (ref "X1") (pin "B11") (pinfunction "B_B11") (pintype "passive"))
    )
    (net (code "168") (name "REG-RD-ID3") (class "Default")
      (node (ref "IC21") (pin "3") (pinfunction "B_3") (pintype "input"))
      (node (ref "X1") (pin "B12") (pinfunction "B_B12") (pintype "passive"))
    )
    (net (code "169") (name "UNUSED0") (class "Default")
      (node (ref "X1") (pin "C12") (pinfunction "B_C12") (pintype "passive"))
    )
    (net (code "170") (name "VCC") (class "Default")
      (node (ref "C1") (pin "1") (pinfunction "1_1") (pintype "passive"))
      (node (ref "C10") (pin "1") (pinfunction "1_1") (pintype "passive"))
      (node (ref "C11") (pin "1") (pinfunction "1_1") (pintype "passive"))
      (node (ref "C12") (pin "1") (pinfunction "1_1") (pintype "passive"))
      (node (ref "C13") (pin "1") (pinfunction "1_1") (pintype "passive"))
      (node (ref "C14") (pin "1") (pinfunction "1_1") (pintype "passive"))
      (node (ref "C15") (pin "1") (pinfunction "1_1") (pintype "passive"))
      (node (ref "C16") (pin "1") (pinfunction "1_1") (pintype "passive"))
      (node (ref "C17") (pin "1") (pinfunction "1_1") (pintype "passive"))
      (node (ref "C18") (pin "1") (pinfunction "1_1") (pintype "passive"))
      (node (ref "C19") (pin "1") (pinfunction "1_1") (pintype "passive"))
      (node (ref "C2") (pin "1") (pinfunction "1_1") (pintype "passive"))
      (node (ref "C20") (pin "1") (pinfunction "1_1") (pintype "passive"))
      (node (ref "C21") (pin "1") (pinfunction "1_1") (pintype "passive"))
      (node (ref "C22") (pin "1") (pinfunction "1_1") (pintype "passive"))
      (node (ref "C3") (pin "1") (pinfunction "1_1") (pintype "passive"))
      (node (ref "C4") (pin "1") (pinfunction "1_1") (pintype "passive"))
      (node (ref "C5") (pin "1") (pinfunction "1_1") (pintype "passive"))
      (node (ref "C6") (pin "1") (pinfunction "1_1") (pintype "passive"))
      (node (ref "C7") (pin "1") (pinfunction "1_1") (pintype "passive"))
      (node (ref "C8") (pin "1") (pinfunction "1_1") (pintype "passive"))
      (node (ref "C9") (pin "1") (pinfunction "1_1") (pintype "passive"))
      (node (ref "IC1") (pin "12") (pinfunction "I0_12") (pintype "input"))
      (node (ref "IC1") (pin "4") (pinfunction "I0_4") (pintype "input"))
      (node (ref "IC1") (pin "9") (pinfunction "I0_9") (pintype "input"))
      (node (ref "JP1") (pin "1") (pinfunction "1_1") (pintype "passive"))
      (node (ref "JP1") (pin "2") (pinfunction "2_2") (pintype "passive"))
      (node (ref "R1") (pin "2") (pinfunction "2_2") (pintype "passive"))
      (node (ref "R2") (pin "2") (pinfunction "2_2") (pintype "passive"))
      (node (ref "RN1") (pin "1") (pinfunction "1_1") (pintype "passive"))
      (node (ref "RN2") (pin "1") (pinfunction "1_1") (pintype "passive"))
      (node (ref "X1") (pin "A2") (pinfunction "B_A2") (pintype "passive"))
      (node (ref "X1") (pin "A31") (pinfunction "B_A31") (pintype "passive"))
      (node (ref "X1") (pin "B2") (pinfunction "B_B2") (pintype "passive"))
      (node (ref "X1") (pin "B31") (pinfunction "B_B31") (pintype "passive"))
      (node (ref "X1") (pin "C2") (pinfunction "B_C2") (pintype "passive"))
      (node (ref "X1") (pin "C31") (pinfunction "B_C31") (pintype "passive"))
    )
    (net (code "171") (name "unconnected-(JP1-Pad27)") (class "Default")
      (node (ref "JP1") (pin "27") (pinfunction "27_27") (pintype "passive"))
    )
    (net (code "172") (name "unconnected-(JP1-Pad28)") (class "Default")
      (node (ref "JP1") (pin "28") (pinfunction "28_28") (pintype "passive"))
    )
    (net (code "173") (name "unconnected-(JP1-Pad29)") (class "Default")
      (node (ref "JP1") (pin "29") (pinfunction "29_29") (pintype "passive"))
    )
    (net (code "174") (name "unconnected-(JP1-Pad30)") (class "Default")
      (node (ref "JP1") (pin "30") (pinfunction "30_30") (pintype "passive"))
    )
    (net (code "175") (name "unconnected-(JP1-Pad31)") (class "Default")
      (node (ref "JP1") (pin "31") (pinfunction "31_31") (pintype "passive"))
    )
    (net (code "176") (name "unconnected-(JP1-Pad32)") (class "Default")
      (node (ref "JP1") (pin "32") (pinfunction "32_32") (pintype "passive"))
    )
    (net (code "177") (name "unconnected-(JP1-Pad33)") (class "Default")
      (node (ref "JP1") (pin "33") (pinfunction "33_33") (pintype "passive"))
    )
    (net (code "178") (name "unconnected-(JP1-Pad34)") (class "Default")
      (node (ref "JP1") (pin "34") (pinfunction "34_34") (pintype "passive"))
    )
    (net (code "179") (name "unconnected-(JP1-Pad35)") (class "Default")
      (node (ref "JP1") (pin "35") (pinfunction "35_35") (pintype "passive"))
    )
    (net (code "180") (name "unconnected-(JP1-Pad36)") (class "Default")
      (node (ref "JP1") (pin "36") (pinfunction "36_36") (pintype "passive"))
    )
    (net (code "181") (name "unconnected-(JP1-Pad37)") (class "Default")
      (node (ref "JP1") (pin "37") (pinfunction "37_37") (pintype "passive"))
    )
    (net (code "182") (name "unconnected-(JP1-Pad38)") (class "Default")
      (node (ref "JP1") (pin "38") (pinfunction "38_38") (pintype "passive"))
    )
  )
)
